# PIC16F627.net
KiCad netlist of a schematic drawn in Altium Designer
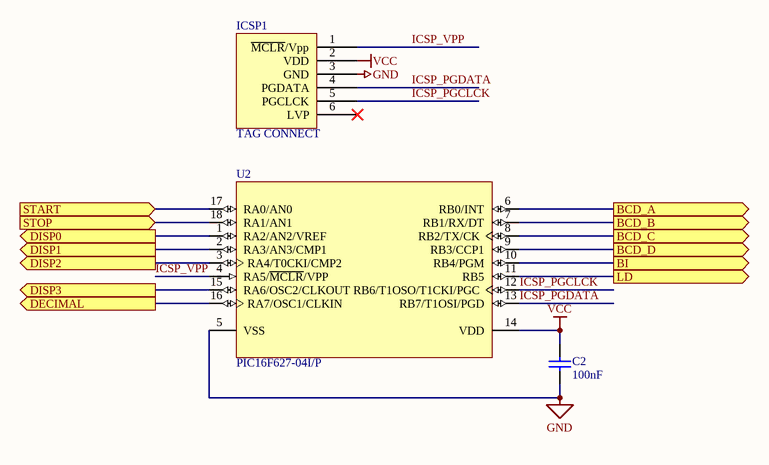
[diagram p0: PIC16F627.SchDoc]

(export (version "E")
  (design (tool "Eeschema 10.0.6"))
  (components
    (comp (ref "C2")
      (value "100nF")
      (footprint "CAP (3D) - 0603")
      (description "Capacitor")
      (fields (field (name "MOUSER PART NO.") "81-GCM188R71C104KA7D") (field (name "MANUFACTURER") "Murata"))
      (libsource (lib "Miscellaneous Devices") (part "Cap"))
    )
    (comp (ref "ICSP1")
      (value "TAG CONNECT")
      (footprint "ICSP - TAG CONNECT")
      (fields (field (name "MANUFACTURER") "N/A - PCB ARTWORK"))
      (libsource (lib "I2C PENDANT") (part "ICSP - TAG CONNECT"))
    )
    (comp (ref "U2")
      (value "PIC16F627-04I/P")
      (footprint "SOIC-18")
      (fields
        (field (name "MOUSER PART NO.") "579-PIC16F627A-I/SO")
        (field (name "MANUFACTURER") "MICROCHIP SEMICONDUCTOR")
        (field (name "MANUFACTURER PART NO.") "PIC16F627A-I/SO")
      )
      (libsource (lib "Microchip Microcontroller 8-Bit PIC16F") (part "PIC16F627-04I/P"))
    )
  )
  (nets
    (net (code "1") (name "/BCD_A") (class "Default")
      (node (ref "U2") (pin "6") (pinfunction "RB0/INT_6") (pintype "bidirectional"))
    )
    (net (code "2") (name "/BCD_B") (class "Default")
      (node (ref "U2") (pin "7") (pinfunction "RB1/RX/DT_7") (pintype "bidirectional"))
    )
    (net (code "3") (name "/BCD_C") (class "Default")
      (node (ref "U2") (pin "8") (pinfunction "RB2/TX/CK_8") (pintype "bidirectional"))
    )
    (net (code "4") (name "/BCD_D") (class "Default")
      (node (ref "U2") (pin "9") (pinfunction "RB3/CCP1_9") (pintype "bidirectional"))
    )
    (net (code "5") (name "/BI") (class "Default")
      (node (ref "U2") (pin "10") (pinfunction "RB4/PGM_10") (pintype "bidirectional"))
    )
    (net (code "6") (name "/DECIMAL") (class "Default")
      (node (ref "U2") (pin "16") (pinfunction "RA7/OSC1/CLKIN_16") (pintype "bidirectional"))
    )
    (net (code "7") (name "/DISP0") (class "Default")
      (node (ref "U2") (pin "1") (pinfunction "RA2/AN2/VREF_1") (pintype "bidirectional"))
    )
    (net (code "8") (name "/DISP1") (class "Default")
      (node (ref "U2") (pin "2") (pinfunction "RA3/AN3/CMP1_2") (pintype "bidirectional"))
    )
    (net (code "9") (name "/DISP2") (class "Default")
      (node (ref "U2") (pin "3") (pinfunction "RA4/T0CKI/CMP2_3") (pintype "bidirectional"))
    )
    (net (code "10") (name "/DISP3") (class "Default")
      (node (ref "U2") (pin "15") (pinfunction "RA6/OSC2/CLKOUT_15") (pintype "bidirectional"))
    )
    (net (code "11") (name "/ICSP_PGCLCK") (class "Default")
      (node (ref "ICSP1") (pin "5") (pinfunction "PGCLCK_5") (pintype "passive"))
      (node (ref "U2") (pin "12") (pinfunction "RB6/T1OSO/T1CKI/PGC_12") (pintype "bidirectional"))
    )
    (net (code "12") (name "/ICSP_PGDATA") (class "Default")
      (node (ref "ICSP1") (pin "4") (pinfunction "PGDATA_4") (pintype "passive"))
      (node (ref "U2") (pin "13") (pinfunction "RB7/T1OSI/PGD_13") (pintype "bidirectional"))
    )
    (net (code "13") (name "/ICSP_VPP") (class "Default")
      (node (ref "ICSP1") (pin "1") (pinfunction "~{MCLR}/Vpp_1") (pintype "passive"))
      (node (ref "U2") (pin "4") (pinfunction "RA5/~{MCLR}/VPP_4") (pintype "input"))
    )
    (net (code "14") (name "/LD") (class "Default")
      (node (ref "U2") (pin "11") (pinfunction "RB5_11") (pintype "bidirectional"))
    )
    (net (code "15") (name "/START") (class "Default")
      (node (ref "U2") (pin "17") (pinfunction "RA0/AN0_17") (pintype "bidirectional"))
    )
    (net (code "16") (name "/STOP") (class "Default")
      (node (ref "U2") (pin "18") (pinfunction "RA1/AN1_18") (pintype "bidirectional"))
    )
    (net (code "17") (name "GND") (class "Default")
      (node (ref "C2") (pin "1") (pinfunction "1_1") (pintype "passive"))
      (node (ref "ICSP1") (pin "3") (pinfunction "GND_3") (pintype "passive"))
      (node (ref "U2") (pin "5") (pinfunction "VSS_5") (pintype "power_in"))
    )
    (net (code "18") (name "VCC") (class "Default")
      (node (ref "C2") (pin "2") (pinfunction "2_2") (pintype "passive"))
      (node (ref "ICSP1") (pin "2") (pinfunction "VDD_2") (pintype "passive"))
      (node (ref "U2") (pin "14") (pinfunction "VDD_14") (pintype "power_in"))
    )
    (net (code "19") (name "unconnected-(ICSP1-LVP-Pad6)") (class "Default")
      (node (ref "ICSP1") (pin "6") (pinfunction "LVP_6") (pintype "passive+no_connect"))
    )
  )
)
